# Peripheral.net
KiCad netlist of a schematic drawn in Altium Designer
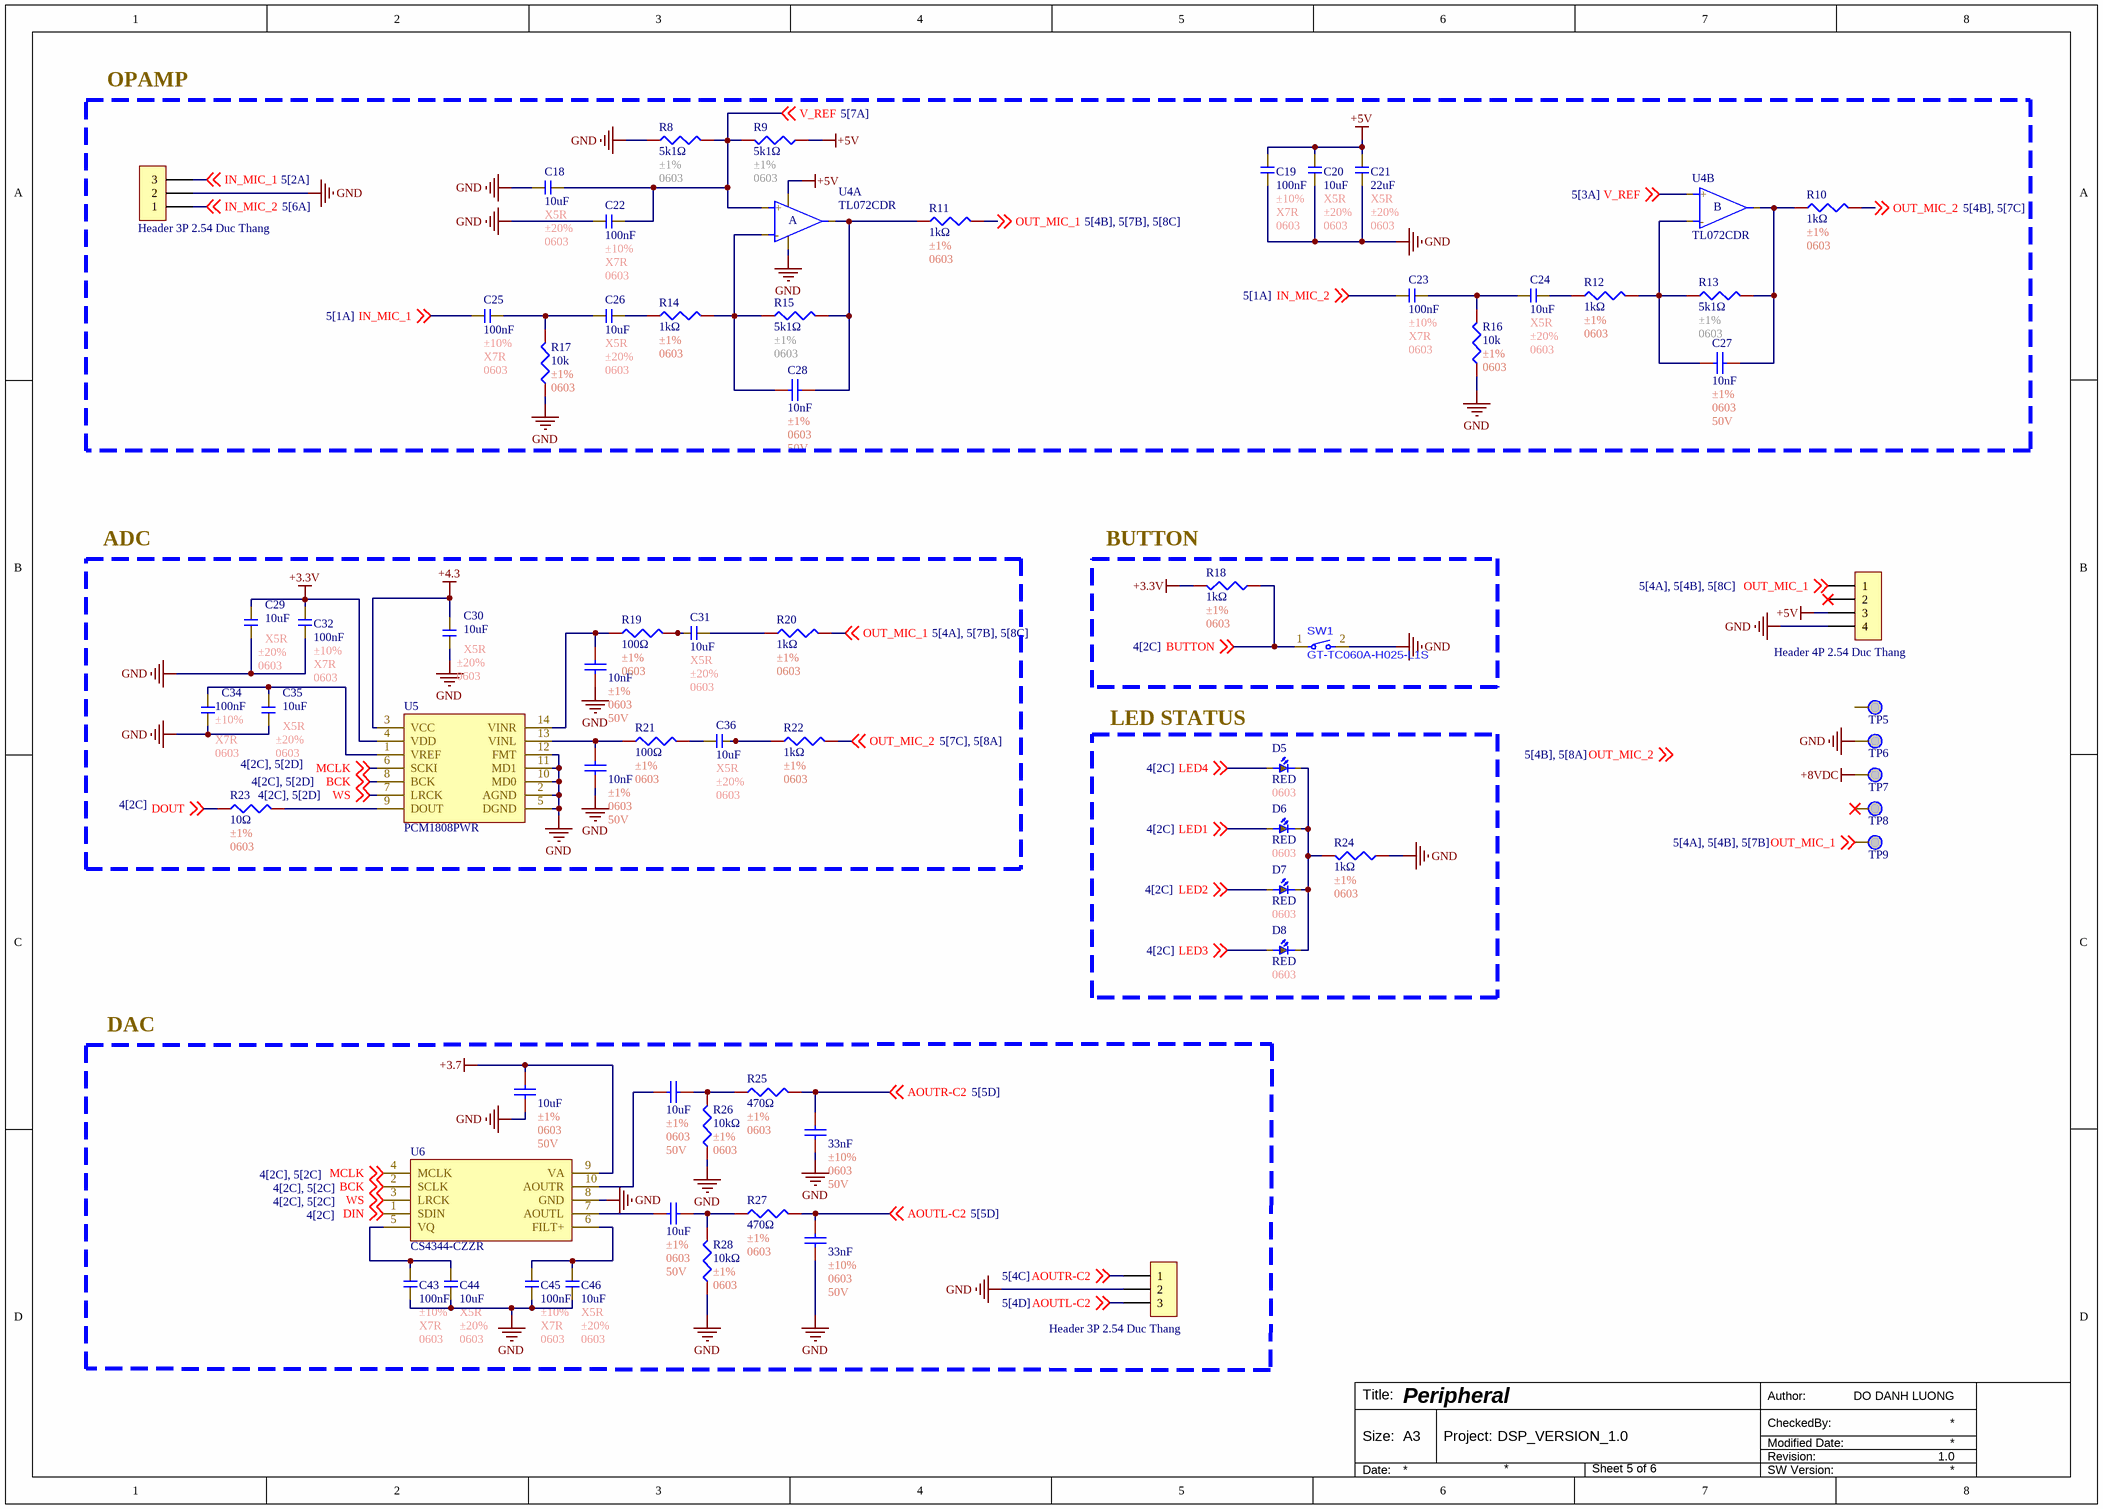
[diagram p0: Peripheral.SchDoc]

(export (version "E")
  (design (tool "Eeschema 10.0.6"))
  (components
    (comp (ref "C18")
      (value "10uF")
      (footprint "C0603")
      (description "25V 10uF X5R ±20% 0603 Multilayer Ceramic Capacitors MLCC - SMD/SMT ROHS")
      (fields
        (field (name "MANUFACTURER") "YAGEO")
        (field (name "MFR. PART #") "CC0603MRX5R8BB106")
        (field (name "TEMPERATURE COEFFICIENT") "X5R")
        (field (name "TOLERANCE") "±20%")
        (field (name "PACKAGE") "0603")
      )
      (libsource (lib "DSP_VERSION_1.0") (part "C0603_10uF_±10%_X7R"))
    )
    (comp (ref "C19")
      (value "100nF")
      (footprint "C0603")
      (description "50V 100nF X7R ±10% 0603 Multilayer Ceramic Capacitors MLCC - SMD/SMT ROHS")
      (fields
        (field (name "MANUFACTURER") "YAGEO")
        (field (name "MFR. PART #") "CC0603KRX7R9BB104")
        (field (name "TOLERANCE") "±10%")
        (field (name "TEMPERATURE COEFFICIENT") "X7R")
        (field (name "PACKAGE") "0603")
      )
      (libsource (lib "DSP_VERSION_1.0") (part "C0603_100nF_±10%_X7R"))
    )
    (comp (ref "C20")
      (value "10uF")
      (footprint "C0603")
      (description "25V 10uF X5R ±20% 0603 Multilayer Ceramic Capacitors MLCC - SMD/SMT ROHS")
      (fields
        (field (name "MANUFACTURER") "YAGEO")
        (field (name "MFR. PART #") "CC0603MRX5R8BB106")
        (field (name "TEMPERATURE COEFFICIENT") "X5R")
        (field (name "TOLERANCE") "±20%")
        (field (name "PACKAGE") "0603")
      )
      (libsource (lib "DSP_VERSION_1.0") (part "C0603_10uF_±10%_X7R"))
    )
    (comp (ref "C21")
      (value "22uF")
      (footprint "C0603")
      (description "6.3V 22uF X5R ±20% 0603 Multilayer Ceramic Capacitors MLCC - SMD/SMT ROHS")
      (fields
        (field (name "MANUFACTURER") "YAGEO")
        (field (name "MFR. PART #") "CC0603MRX5R5BB226")
        (field (name "TEMPERATURE COEFFICIENT") "X5R")
        (field (name "TOLERANCE") "±20%")
        (field (name "PACKAGE") "0603")
      )
      (libsource (lib "DSP_VERSION_1.0") (part "C0603_22uF_±20%_X5R"))
    )
    (comp (ref "C22")
      (value "100nF")
      (footprint "C0603")
      (description "50V 100nF X7R ±10% 0603 Multilayer Ceramic Capacitors MLCC - SMD/SMT ROHS")
      (fields
        (field (name "MANUFACTURER") "YAGEO")
        (field (name "MFR. PART #") "CC0603KRX7R9BB104")
        (field (name "TOLERANCE") "±10%")
        (field (name "TEMPERATURE COEFFICIENT") "X7R")
        (field (name "PACKAGE") "0603")
      )
      (libsource (lib "DSP_VERSION_1.0") (part "C0603_100nF_±10%_X7R"))
    )
    (comp (ref "C23")
      (value "100nF")
      (footprint "C0603")
      (description "50V 100nF X7R ±10% 0603 Multilayer Ceramic Capacitors MLCC - SMD/SMT ROHS")
      (fields
        (field (name "MANUFACTURER") "YAGEO")
        (field (name "MFR. PART #") "CC0603KRX7R9BB104")
        (field (name "TOLERANCE") "±10%")
        (field (name "TEMPERATURE COEFFICIENT") "X7R")
        (field (name "PACKAGE") "0603")
      )
      (libsource (lib "DSP_VERSION_1.0") (part "C0603_100nF_±10%_X7R"))
    )
    (comp (ref "C24")
      (value "10uF")
      (footprint "C0603")
      (description "25V 10uF X5R ±20% 0603 Multilayer Ceramic Capacitors MLCC - SMD/SMT ROHS")
      (fields
        (field (name "MANUFACTURER") "YAGEO")
        (field (name "MFR. PART #") "CC0603MRX5R8BB106")
        (field (name "TEMPERATURE COEFFICIENT") "X5R")
        (field (name "TOLERANCE") "±20%")
        (field (name "PACKAGE") "0603")
      )
      (libsource (lib "DSP_VERSION_1.0") (part "C0603_10uF_±10%_X7R"))
    )
    (comp (ref "C25")
      (value "100nF")
      (footprint "C0603")
      (description "50V 100nF X7R ±10% 0603 Multilayer Ceramic Capacitors MLCC - SMD/SMT ROHS")
      (fields
        (field (name "MANUFACTURER") "YAGEO")
        (field (name "MFR. PART #") "CC0603KRX7R9BB104")
        (field (name "TOLERANCE") "±10%")
        (field (name "TEMPERATURE COEFFICIENT") "X7R")
        (field (name "PACKAGE") "0603")
      )
      (libsource (lib "DSP_VERSION_1.0") (part "C0603_100nF_±10%_X7R"))
    )
    (comp (ref "C26")
      (value "10uF")
      (footprint "C0603")
      (description "25V 10uF X5R ±20% 0603 Multilayer Ceramic Capacitors MLCC - SMD/SMT ROHS")
      (fields
        (field (name "MANUFACTURER") "YAGEO")
        (field (name "MFR. PART #") "CC0603MRX5R8BB106")
        (field (name "TEMPERATURE COEFFICIENT") "X5R")
        (field (name "TOLERANCE") "±20%")
        (field (name "PACKAGE") "0603")
      )
      (libsource (lib "DSP_VERSION_1.0") (part "C0603_10uF_±10%_X7R"))
    )
    (comp (ref "C27")
      (value "10nF")
      (footprint "C0603")
      (description "50V 10pF NP0 ±1% 0402 Multilayer Ceramic Capacitors MLCC - SMD/SMT ROHS")
      (fields
        (field (name "MANUFACTURER") "YAGEO")
        (field (name "MFR. PART #") "CC0402FRNPO9BN100")
        (field (name "TOLERANCE") "±1%")
        (field (name "PACKAGE") "0603")
        (field (name "VOLTAGE RATING") "50V")
      )
      (libsource (lib "Capital") (part "C0603_10nF_±1%"))
    )
    (comp (ref "C28")
      (value "10nF")
      (footprint "C0603")
      (description "50V 10pF NP0 ±1% 0402 Multilayer Ceramic Capacitors MLCC - SMD/SMT ROHS")
      (fields
        (field (name "MANUFACTURER") "YAGEO")
        (field (name "MFR. PART #") "CC0402FRNPO9BN100")
        (field (name "TOLERANCE") "±1%")
        (field (name "PACKAGE") "0603")
        (field (name "VOLTAGE RATING") "50V")
      )
      (libsource (lib "Capital") (part "C0603_10nF_±1%"))
    )
    (comp (ref "C29")
      (value "10uF")
      (footprint "C0603")
      (description "25V 10uF X5R ±20% 0603 Multilayer Ceramic Capacitors MLCC - SMD/SMT ROHS")
      (fields
        (field (name "MANUFACTURER") "YAGEO")
        (field (name "MFR. PART #") "CC0603MRX5R8BB106")
        (field (name "TEMPERATURE COEFFICIENT") "X5R")
        (field (name "TOLERANCE") "±20%")
        (field (name "PACKAGE") "0603")
      )
      (libsource (lib "DSP_VERSION_1.0") (part "C0603_10uF_±10%_X7R"))
    )
    (comp (ref "C30")
      (value "10uF")
      (footprint "C0603")
      (description "25V 10uF X5R ±20% 0603 Multilayer Ceramic Capacitors MLCC - SMD/SMT ROHS")
      (fields
        (field (name "MANUFACTURER") "YAGEO")
        (field (name "MFR. PART #") "CC0603MRX5R8BB106")
        (field (name "TEMPERATURE COEFFICIENT") "X5R")
        (field (name "TOLERANCE") "±20%")
        (field (name "PACKAGE") "0603")
      )
      (libsource (lib "DSP_VERSION_1.0") (part "C0603_10uF_±10%_X7R"))
    )
    (comp (ref "C31")
      (value "10uF")
      (footprint "C0603")
      (description "25V 10uF X5R ±20% 0603 Multilayer Ceramic Capacitors MLCC - SMD/SMT ROHS")
      (fields
        (field (name "MANUFACTURER") "YAGEO")
        (field (name "MFR. PART #") "CC0603MRX5R8BB106")
        (field (name "TEMPERATURE COEFFICIENT") "X5R")
        (field (name "TOLERANCE") "±20%")
        (field (name "PACKAGE") "0603")
      )
      (libsource (lib "DSP_VERSION_1.0") (part "C0603_10uF_±10%_X7R"))
    )
    (comp (ref "C32")
      (value "100nF")
      (footprint "C0603")
      (description "50V 100nF X7R ±10% 0603 Multilayer Ceramic Capacitors MLCC - SMD/SMT ROHS")
      (fields
        (field (name "MANUFACTURER") "YAGEO")
        (field (name "MFR. PART #") "CC0603KRX7R9BB104")
        (field (name "TOLERANCE") "±10%")
        (field (name "TEMPERATURE COEFFICIENT") "X7R")
        (field (name "PACKAGE") "0603")
      )
      (libsource (lib "DSP_VERSION_1.0") (part "C0603_100nF_±10%_X7R"))
    )
    (comp (ref "C33")
      (value "10nF")
      (footprint "C0603")
      (description "50V 10pF NP0 ±1% 0402 Multilayer Ceramic Capacitors MLCC - SMD/SMT ROHS")
      (fields
        (field (name "MANUFACTURER") "YAGEO")
        (field (name "MFR. PART #") "CC0402FRNPO9BN100")
        (field (name "TOLERANCE") "±1%")
        (field (name "PACKAGE") "0603")
        (field (name "VOLTAGE RATING") "50V")
      )
      (libsource (lib "Capital") (part "C0603_10nF_±1%"))
    )
    (comp (ref "C34")
      (value "100nF")
      (footprint "C0603")
      (description "50V 100nF X7R ±10% 0603 Multilayer Ceramic Capacitors MLCC - SMD/SMT ROHS")
      (fields
        (field (name "MANUFACTURER") "YAGEO")
        (field (name "MFR. PART #") "CC0603KRX7R9BB104")
        (field (name "TOLERANCE") "±10%")
        (field (name "TEMPERATURE COEFFICIENT") "X7R")
        (field (name "PACKAGE") "0603")
      )
      (libsource (lib "DSP_VERSION_1.0") (part "C0603_100nF_±10%_X7R"))
    )
    (comp (ref "C35")
      (value "10uF")
      (footprint "C0603")
      (description "25V 10uF X5R ±20% 0603 Multilayer Ceramic Capacitors MLCC - SMD/SMT ROHS")
      (fields
        (field (name "MANUFACTURER") "YAGEO")
        (field (name "MFR. PART #") "CC0603MRX5R8BB106")
        (field (name "TEMPERATURE COEFFICIENT") "X5R")
        (field (name "TOLERANCE") "±20%")
        (field (name "PACKAGE") "0603")
      )
      (libsource (lib "DSP_VERSION_1.0") (part "C0603_10uF_±10%_X7R"))
    )
    (comp (ref "C36")
      (value "10uF")
      (footprint "C0603")
      (description "25V 10uF X5R ±20% 0603 Multilayer Ceramic Capacitors MLCC - SMD/SMT ROHS")
      (fields
        (field (name "MANUFACTURER") "YAGEO")
        (field (name "MFR. PART #") "CC0603MRX5R8BB106")
        (field (name "TEMPERATURE COEFFICIENT") "X5R")
        (field (name "TOLERANCE") "±20%")
        (field (name "PACKAGE") "0603")
      )
      (libsource (lib "DSP_VERSION_1.0") (part "C0603_10uF_±10%_X7R"))
    )
    (comp (ref "C37")
      (value "10nF")
      (footprint "C0603")
      (description "50V 10pF NP0 ±1% 0402 Multilayer Ceramic Capacitors MLCC - SMD/SMT ROHS")
      (fields
        (field (name "MANUFACTURER") "YAGEO")
        (field (name "MFR. PART #") "CC0402FRNPO9BN100")
        (field (name "TOLERANCE") "±1%")
        (field (name "PACKAGE") "0603")
        (field (name "VOLTAGE RATING") "50V")
      )
      (libsource (lib "Capital") (part "C0603_10nF_±1%"))
    )
    (comp (ref "C38")
      (value "10uF")
      (footprint "C0603")
      (description "50V 10pF NP0 ±1% 0402 Multilayer Ceramic Capacitors MLCC - SMD/SMT ROHS")
      (fields
        (field (name "MANUFACTURER") "YAGEO")
        (field (name "MFR. PART #") "CC0402FRNPO9BN100")
        (field (name "TOLERANCE") "±1%")
        (field (name "PACKAGE") "0603")
        (field (name "VOLTAGE RATING") "50V")
      )
      (libsource (lib "Capital") (part "C0603_10uF_±1%"))
    )
    (comp (ref "C39")
      (value "10uF")
      (footprint "C0603")
      (description "50V 10pF NP0 ±1% 0402 Multilayer Ceramic Capacitors MLCC - SMD/SMT ROHS")
      (fields
        (field (name "MANUFACTURER") "YAGEO")
        (field (name "MFR. PART #") "CC0402FRNPO9BN100")
        (field (name "TOLERANCE") "±1%")
        (field (name "PACKAGE") "0603")
        (field (name "VOLTAGE RATING") "50V")
      )
      (libsource (lib "Capital") (part "C0603_10uF_±1%"))
    )
    (comp (ref "C40")
      (value "33nF")
      (footprint "C0603")
      (description "100mW Thick Film Resistor 75V ±100ppm/℃ ±1% 470Ω 0603 Chip Resistor - Surface Mount ROHS")
      (fields
        (field (name "MANUFACTURER") "YAGEO")
        (field (name "MFR. PART #") "CC0603KRX7R9BB333")
        (field (name "TOLERANCE") "±10%")
        (field (name "PACKAGE") "0603")
        (field (name "VOLTAGE RATING") "50V")
      )
      (libsource (lib "Capital") (part "C0603_33nF_±10%"))
    )
    (comp (ref "C41")
      (value "10uF")
      (footprint "C0603")
      (description "50V 10pF NP0 ±1% 0402 Multilayer Ceramic Capacitors MLCC - SMD/SMT ROHS")
      (fields
        (field (name "MANUFACTURER") "YAGEO")
        (field (name "MFR. PART #") "CC0402FRNPO9BN100")
        (field (name "TOLERANCE") "±1%")
        (field (name "PACKAGE") "0603")
        (field (name "VOLTAGE RATING") "50V")
      )
      (libsource (lib "Capital") (part "C0603_10uF_±1%"))
    )
    (comp (ref "C42")
      (value "33nF")
      (footprint "C0603")
      (description "100mW Thick Film Resistor 75V ±100ppm/℃ ±1% 470Ω 0603 Chip Resistor - Surface Mount ROHS")
      (fields
        (field (name "MANUFACTURER") "YAGEO")
        (field (name "MFR. PART #") "CC0603KRX7R9BB333")
        (field (name "TOLERANCE") "±10%")
        (field (name "PACKAGE") "0603")
        (field (name "VOLTAGE RATING") "50V")
      )
      (libsource (lib "Capital") (part "C0603_33nF_±10%"))
    )
    (comp (ref "C43")
      (value "100nF")
      (footprint "C0603")
      (description "50V 100nF X7R ±10% 0603 Multilayer Ceramic Capacitors MLCC - SMD/SMT ROHS")
      (fields
        (field (name "MANUFACTURER") "YAGEO")
        (field (name "MFR. PART #") "CC0603KRX7R9BB104")
        (field (name "TOLERANCE") "±10%")
        (field (name "TEMPERATURE COEFFICIENT") "X7R")
        (field (name "PACKAGE") "0603")
      )
      (libsource (lib "DSP_VERSION_1.0") (part "C0603_100nF_±10%_X7R"))
    )
    (comp (ref "C44")
      (value "10uF")
      (footprint "C0603")
      (description "25V 10uF X5R ±20% 0603 Multilayer Ceramic Capacitors MLCC - SMD/SMT ROHS")
      (fields
        (field (name "MANUFACTURER") "YAGEO")
        (field (name "MFR. PART #") "CC0603MRX5R8BB106")
        (field (name "TEMPERATURE COEFFICIENT") "X5R")
        (field (name "TOLERANCE") "±20%")
        (field (name "PACKAGE") "0603")
      )
      (libsource (lib "DSP_VERSION_1.0") (part "C0603_10uF_±10%_X7R"))
    )
    (comp (ref "C45")
      (value "100nF")
      (footprint "C0603")
      (description "50V 100nF X7R ±10% 0603 Multilayer Ceramic Capacitors MLCC - SMD/SMT ROHS")
      (fields
        (field (name "MANUFACTURER") "YAGEO")
        (field (name "MFR. PART #") "CC0603KRX7R9BB104")
        (field (name "TOLERANCE") "±10%")
        (field (name "TEMPERATURE COEFFICIENT") "X7R")
        (field (name "PACKAGE") "0603")
      )
      (libsource (lib "DSP_VERSION_1.0") (part "C0603_100nF_±10%_X7R"))
    )
    (comp (ref "C46")
      (value "10uF")
      (footprint "C0603")
      (description "25V 10uF X5R ±20% 0603 Multilayer Ceramic Capacitors MLCC - SMD/SMT ROHS")
      (fields
        (field (name "MANUFACTURER") "YAGEO")
        (field (name "MFR. PART #") "CC0603MRX5R8BB106")
        (field (name "TEMPERATURE COEFFICIENT") "X5R")
        (field (name "TOLERANCE") "±20%")
        (field (name "PACKAGE") "0603")
      )
      (libsource (lib "DSP_VERSION_1.0") (part "C0603_10uF_±10%_X7R"))
    )
    (comp (ref "D5")
      (value "RED")
      (footprint "LED0603")
      (description "25mcd~40mcd Water Clear -40℃~+85℃ 624nm Red 120° 60mW 0402 LED Indication - Discrete ROHS")
      (fields
        (field (name "MANUFACTURER") "XINGLIGHT")
        (field (name "MFR. PART #") "XL-1005UGC")
        (field (name "PACKAGE") "0603")
      )
      (libsource (lib "LED") (part "D0603_RED"))
    )
    (comp (ref "D6")
      (value "RED")
      (footprint "LED0603")
      (description "25mcd~40mcd Water Clear -40℃~+85℃ 624nm Red 120° 60mW 0402 LED Indication - Discrete ROHS")
      (fields
        (field (name "MANUFACTURER") "XINGLIGHT")
        (field (name "MFR. PART #") "XL-1005UGC")
        (field (name "PACKAGE") "0603")
      )
      (libsource (lib "LED") (part "D0603_RED"))
    )
    (comp (ref "D7")
      (value "RED")
      (footprint "LED0603")
      (description "25mcd~40mcd Water Clear -40℃~+85℃ 624nm Red 120° 60mW 0402 LED Indication - Discrete ROHS")
      (fields
        (field (name "MANUFACTURER") "XINGLIGHT")
        (field (name "MFR. PART #") "XL-1005UGC")
        (field (name "PACKAGE") "0603")
      )
      (libsource (lib "LED") (part "D0603_RED"))
    )
    (comp (ref "D8")
      (value "RED")
      (footprint "LED0603")
      (description "25mcd~40mcd Water Clear -40℃~+85℃ 624nm Red 120° 60mW 0402 LED Indication - Discrete ROHS")
      (fields
        (field (name "MANUFACTURER") "XINGLIGHT")
        (field (name "MFR. PART #") "XL-1005UGC")
        (field (name "PACKAGE") "0603")
      )
      (libsource (lib "LED") (part "D0603_RED"))
    )
    (comp (ref "H1")
      (value "Header 3P 2.54 Duc Thang")
      (footprint "XH2.54M-3")
      (description "Cắm")
      (libsource (lib "Header") (part "Header 3P 2.54 Duc Thang"))
    )
    (comp (ref "H2")
      (value "Header 4P 2.54 Duc Thang")
      (footprint "XH2.54M-4")
      (description "Cắm")
      (libsource (lib "Header") (part "Header 4P 2.54 Duc Thang"))
    )
    (comp (ref "H3")
      (value "Header 3P 2.54 Duc Thang")
      (footprint "XH2.54M-3")
      (description "Cắm")
      (libsource (lib "") (part "Header 3P 2.54 Duc Thang_1"))
    )
    (comp (ref "R8")
      (value "5k1Ω")
      (footprint "R0603")
      (description "100mW Thick Film Resistor 75V ±100ppm/℃ ±1% 5.1kΩ 0603 Chip Resistor - Surface Mount ROHS")
      (fields
        (field (name "MANUFACTURER") "FOJAN")
        (field (name "MFR. PART #") "FRC0603F5101TS")
        (field (name "TOLERANCE") "±1%")
        (field (name "PACKAGE") "0603")
      )
      (libsource (lib "Resistor") (part "R0603_5k1Ω_±1%"))
    )
    (comp (ref "R9")
      (value "5k1Ω")
      (footprint "R0603")
      (description "100mW Thick Film Resistor 75V ±100ppm/℃ ±1% 5.1kΩ 0603 Chip Resistor - Surface Mount ROHS")
      (fields
        (field (name "MANUFACTURER") "FOJAN")
        (field (name "MFR. PART #") "FRC0603F5101TS")
        (field (name "TOLERANCE") "±1%")
        (field (name "PACKAGE") "0603")
      )
      (libsource (lib "Resistor") (part "R0603_5k1Ω_±1%"))
    )
    (comp (ref "R10")
      (value "1kΩ")
      (footprint "R0603")
      (description "62.5mW Thick Film Resistor 50V ±1% ±200ppm/℃ 10Ω 0402 Chip Resistor - Surface Mount ROHS")
      (fields
        (field (name "MANUFACTURER") "YAGEO")
        (field (name "MFR. PART #") "RC0402FR-0710RL")
        (field (name "TOLERANCE") "±1%")
        (field (name "PACKAGE") "0603")
      )
      (libsource (lib "Resistor") (part "R0603_1kΩ_±1%"))
    )
    (comp (ref "R11")
      (value "1kΩ")
      (footprint "R0603")
      (description "62.5mW Thick Film Resistor 50V ±1% ±200ppm/℃ 10Ω 0402 Chip Resistor - Surface Mount ROHS")
      (fields
        (field (name "MANUFACTURER") "YAGEO")
        (field (name "MFR. PART #") "RC0402FR-0710RL")
        (field (name "TOLERANCE") "±1%")
        (field (name "PACKAGE") "0603")
      )
      (libsource (lib "Resistor") (part "R0603_1kΩ_±1%"))
    )
    (comp (ref "R12")
      (value "1kΩ")
      (footprint "R0603")
      (description "62.5mW Thick Film Resistor 50V ±1% ±200ppm/℃ 10Ω 0402 Chip Resistor - Surface Mount ROHS")
      (fields
        (field (name "MANUFACTURER") "YAGEO")
        (field (name "MFR. PART #") "RC0402FR-0710RL")
        (field (name "TOLERANCE") "±1%")
        (field (name "PACKAGE") "0603")
      )
      (libsource (lib "Resistor") (part "R0603_1kΩ_±1%"))
    )
    (comp (ref "R13")
      (value "5k1Ω")
      (footprint "R0603")
      (description "100mW Thick Film Resistor 75V ±100ppm/℃ ±1% 5.1kΩ 0603 Chip Resistor - Surface Mount ROHS")
      (fields
        (field (name "MANUFACTURER") "FOJAN")
        (field (name "MFR. PART #") "FRC0603F5101TS")
        (field (name "TOLERANCE") "±1%")
        (field (name "PACKAGE") "0603")
      )
      (libsource (lib "Resistor") (part "R0603_5k1Ω_±1%"))
    )
    (comp (ref "R14")
      (value "1kΩ")
      (footprint "R0603")
      (description "62.5mW Thick Film Resistor 50V ±1% ±200ppm/℃ 10Ω 0402 Chip Resistor - Surface Mount ROHS")
      (fields
        (field (name "MANUFACTURER") "YAGEO")
        (field (name "MFR. PART #") "RC0402FR-0710RL")
        (field (name "TOLERANCE") "±1%")
        (field (name "PACKAGE") "0603")
      )
      (libsource (lib "Resistor") (part "R0603_1kΩ_±1%"))
    )
    (comp (ref "R15")
      (value "5k1Ω")
      (footprint "R0603")
      (description "100mW Thick Film Resistor 75V ±100ppm/℃ ±1% 5.1kΩ 0603 Chip Resistor - Surface Mount ROHS")
      (fields
        (field (name "MANUFACTURER") "FOJAN")
        (field (name "MFR. PART #") "FRC0603F5101TS")
        (field (name "TOLERANCE") "±1%")
        (field (name "PACKAGE") "0603")
      )
      (libsource (lib "Resistor") (part "R0603_5k1Ω_±1%"))
    )
    (comp (ref "R16")
      (value "10k")
      (footprint "R0603")
      (description "62.5mW Thick Film Resistor 50V ±1% ±200ppm/℃ 10Ω 0402 Chip Resistor - Surface Mount ROHS")
      (fields
        (field (name "MANUFACTURER") "YAGEO")
        (field (name "MFR. PART #") "RC0402FR-0710RL")
        (field (name "TOLERANCE") "±1%")
        (field (name "PACKAGE") "0603")
      )
      (libsource (lib "Resistor") (part "R0603_1kΩ_±1%"))
    )
    (comp (ref "R17")
      (value "10k")
      (footprint "R0603")
      (description "62.5mW Thick Film Resistor 50V ±1% ±200ppm/℃ 10Ω 0402 Chip Resistor - Surface Mount ROHS")
      (fields
        (field (name "MANUFACTURER") "YAGEO")
        (field (name "MFR. PART #") "RC0402FR-0710RL")
        (field (name "TOLERANCE") "±1%")
        (field (name "PACKAGE") "0603")
      )
      (libsource (lib "Resistor") (part "R0603_1kΩ_±1%"))
    )
    (comp (ref "R18")
      (value "1kΩ")
      (footprint "R0603")
      (description "62.5mW Thick Film Resistor 50V ±1% ±200ppm/℃ 10Ω 0402 Chip Resistor - Surface Mount ROHS")
      (fields
        (field (name "MANUFACTURER") "YAGEO")
        (field (name "MFR. PART #") "RC0402FR-0710RL")
        (field (name "TOLERANCE") "±1%")
        (field (name "PACKAGE") "0603")
      )
      (libsource (lib "Resistor") (part "R0603_1kΩ_±1%"))
    )
    (comp (ref "R19")
      (value "100Ω")
      (footprint "R0603")
      (description "62.5mW Thick Film Resistor 50V ±1% ±200ppm/℃ 10Ω 0402 Chip Resistor - Surface Mount ROHS")
      (fields
        (field (name "MANUFACTURER") "YAGEO")
        (field (name "MFR. PART #") "RC0402FR-0710RL")
        (field (name "TOLERANCE") "±1%")
        (field (name "PACKAGE") "0603")
      )
      (libsource (lib "Resistor") (part "R0603_100Ω_±1%"))
    )
    (comp (ref "R20")
      (value "1kΩ")
      (footprint "R0603")
      (description "62.5mW Thick Film Resistor 50V ±1% ±200ppm/℃ 10Ω 0402 Chip Resistor - Surface Mount ROHS")
      (fields
        (field (name "MANUFACTURER") "YAGEO")
        (field (name "MFR. PART #") "RC0402FR-0710RL")
        (field (name "TOLERANCE") "±1%")
        (field (name "PACKAGE") "0603")
      )
      (libsource (lib "Resistor") (part "R0603_1kΩ_±1%"))
    )
    (comp (ref "R21")
      (value "100Ω")
      (footprint "R0603")
      (description "62.5mW Thick Film Resistor 50V ±1% ±200ppm/℃ 10Ω 0402 Chip Resistor - Surface Mount ROHS")
      (fields
        (field (name "MANUFACTURER") "YAGEO")
        (field (name "MFR. PART #") "RC0402FR-0710RL")
        (field (name "TOLERANCE") "±1%")
        (field (name "PACKAGE") "0603")
      )
      (libsource (lib "Resistor") (part "R0603_100Ω_±1%"))
    )
    (comp (ref "R22")
      (value "1kΩ")
      (footprint "R0603")
      (description "62.5mW Thick Film Resistor 50V ±1% ±200ppm/℃ 10Ω 0402 Chip Resistor - Surface Mount ROHS")
      (fields
        (field (name "MANUFACTURER") "YAGEO")
        (field (name "MFR. PART #") "RC0402FR-0710RL")
        (field (name "TOLERANCE") "±1%")
        (field (name "PACKAGE") "0603")
      )
      (libsource (lib "Resistor") (part "R0603_1kΩ_±1%"))
    )
    (comp (ref "R23")
      (value "10Ω")
      (footprint "R0603")
      (description "62.5mW Thick Film Resistor 50V ±1% ±200ppm/℃ 10Ω 0402 Chip Resistor - Surface Mount ROHS")
      (fields
        (field (name "MANUFACTURER") "YAGEO")
        (field (name "MFR. PART #") "RC0402FR-0710RL")
        (field (name "TOLERANCE") "±1%")
        (field (name "PACKAGE") "0603")
      )
      (libsource (lib "Resistor") (part "R0603_10Ω_±1%"))
    )
    (comp (ref "R24")
      (value "1kΩ")
      (footprint "R0603")
      (description "62.5mW Thick Film Resistor 50V ±1% ±200ppm/℃ 10Ω 0402 Chip Resistor - Surface Mount ROHS")
      (fields
        (field (name "MANUFACTURER") "YAGEO")
        (field (name "MFR. PART #") "RC0402FR-0710RL")
        (field (name "TOLERANCE") "±1%")
        (field (name "PACKAGE") "0603")
      )
      (libsource (lib "Resistor") (part "R0603_1kΩ_±1%"))
    )
    (comp (ref "R25")
      (value "470Ω")
      (footprint "R0603")
      (description "62.5mW Thick Film Resistor 50V ±1% ±200ppm/℃ 10Ω 0402 Chip Resistor - Surface Mount ROHS")
      (fields
        (field (name "MANUFACTURER") "YAGEO")
        (field (name "MFR. PART #") "RC0603FR-07470RL")
        (field (name "TOLERANCE") "±1%")
        (field (name "PACKAGE") "0603")
      )
      (libsource (lib "Resistor") (part "R0603_470Ω_±1%_1"))
    )
    (comp (ref "R26")
      (value "10kΩ")
      (footprint "R0603")
      (description "62.5mW Thick Film Resistor 50V ±1% ±200ppm/℃ 10Ω 0402 Chip Resistor - Surface Mount ROHS")
      (fields
        (field (name "MANUFACTURER") "YAGEO")
        (field (name "MFR. PART #") "RC0402FR-0710RL")
        (field (name "TOLERANCE") "±1%")
        (field (name "PACKAGE") "0603")
      )
      (libsource (lib "Resistor") (part "R0603_10kΩ_±1%"))
    )
    (comp (ref "R27")
      (value "470Ω")
      (footprint "R0603")
      (description "62.5mW Thick Film Resistor 50V ±1% ±200ppm/℃ 10Ω 0402 Chip Resistor - Surface Mount ROHS")
      (fields
        (field (name "MANUFACTURER") "YAGEO")
        (field (name "MFR. PART #") "RC0603FR-07470RL")
        (field (name "TOLERANCE") "±1%")
        (field (name "PACKAGE") "0603")
      )
      (libsource (lib "Resistor") (part "R0603_470Ω_±1%_1"))
    )
    (comp (ref "R28")
      (value "10kΩ")
      (footprint "R0603")
      (description "62.5mW Thick Film Resistor 50V ±1% ±200ppm/℃ 10Ω 0402 Chip Resistor - Surface Mount ROHS")
      (fields
        (field (name "MANUFACTURER") "YAGEO")
        (field (name "MFR. PART #") "RC0402FR-0710RL")
        (field (name "TOLERANCE") "±1%")
        (field (name "PACKAGE") "0603")
      )
      (libsource (lib "Resistor") (part "R0603_10kΩ_±1%"))
    )
    (comp (ref "SW1")
      (value "GT-TC060A-H025-L1S")
      (footprint "GT-TC060A-H025-L1S")
      (description "Tactile Switch SPST 160gf 2.5mm SMD (SMT) Tab 6.05mm x 3.5mm Surface Mount")
      (fields (field (name "MANUFACTURER") "G-Switch") (field (name "LCSC PART #") "C7450623"))
      (libsource (lib "Switch") (part "GT-TC060A-H025-L1S"))
    )
    (comp (ref "TP5") (value "TP") (footprint "TP") (libsource (lib "Other") (part "TP")))
    (comp (ref "TP6") (value "TP") (footprint "TP") (libsource (lib "Other") (part "TP")))
    (comp (ref "TP7") (value "TP") (footprint "TP") (libsource (lib "Other") (part "TP")))
    (comp (ref "TP8") (value "TP") (footprint "TP") (libsource (lib "Other") (part "TP")))
    (comp (ref "TP9") (value "TP") (footprint "TP") (libsource (lib "Other") (part "TP")))
    (comp (ref "U4")
      (value "TL072CDR")
      (footprint "TL072CDR")
      (description "3mV 65pA 3MHz 13V/us 2 SOIC-8 FET Input Amplifiers ROHS")
      (fields (field (name "MANUFACTURER") "TI") (field (name "LCSC PART #") "C67473"))
      (libsource (lib "IC") (part "TL072CDR"))
    )
    (comp (ref "U5")
      (value "PCM1808PWR")
      (footprint "PCM1808PWR")
      (description "4.5V~5.5V 24 I2S TSSOP-14 ADCs/DACs - Special Purpose ROHS")
      (fields (field (name "MANUFACTURER") "TI") (field (name "LCSC PART #") "C55513"))
      (libsource (lib "IC") (part "PCM1808PWR"))
    )
    (comp (ref "U6")
      (value "CS4344-CZZR")
      (footprint "CS4344-CZZR")
      (description "250ms I2S 3.3V~5V 24 TSSOP-10-3mm Digital to Analog Converters (DAC) ROHS")
      (fields (field (name "MANUFACTURER") "Cirrus Logic") (field (name "LCSC PART #") "C8952"))
      (libsource (lib "IC") (part "CS4344-CZZR"))
    )
  )
  (nets
    (net (code "1") (name "+3.3V") (class "Default")
      (node (ref "C29") (pin "2") (pinfunction "2_2") (pintype "passive"))
      (node (ref "C32") (pin "2") (pinfunction "2_2") (pintype "passive"))
      (node (ref "R18") (pin "2") (pinfunction "2_2") (pintype "passive"))
      (node (ref "U5") (pin "4") (pinfunction "VDD_4") (pintype "passive"))
    )
    (net (code "2") (name "+3.7") (class "Default")
      (node (ref "C39") (pin "1") (pinfunction "1_1") (pintype "passive"))
      (node (ref "U6") (pin "9") (pinfunction "VA_9") (pintype "passive"))
    )
    (net (code "3") (name "+4.3") (class "Default")
      (node (ref "C30") (pin "2") (pinfunction "2_2") (pintype "passive"))
      (node (ref "U5") (pin "3") (pinfunction "VCC_3") (pintype "passive"))
    )
    (net (code "4") (name "+5V") (class "Default")
      (node (ref "C19") (pin "2") (pinfunction "2_2") (pintype "passive"))
      (node (ref "C20") (pin "2") (pinfunction "2_2") (pintype "passive"))
      (node (ref "C21") (pin "2") (pinfunction "2_2") (pintype "passive"))
      (node (ref "H2") (pin "3") (pinfunction "3_3") (pintype "passive"))
      (node (ref "R9") (pin "1") (pinfunction "1_1") (pintype "passive"))
      (node (ref "U4") (pin "8") (pinfunction "8_8") (pintype "passive"))
    )
    (net (code "5") (name "+8VDC") (class "Default")
      (node (ref "TP7") (pin "1") (pinfunction "1_1") (pintype "passive"))
    )
    (net (code "6") (name "AOUTL-C2") (class "Default")
      (node (ref "C42") (pin "1") (pinfunction "1_1") (pintype "passive"))
      (node (ref "H3") (pin "3") (pinfunction "3_3") (pintype "passive"))
      (node (ref "R27") (pin "2") (pinfunction "2_2") (pintype "passive"))
    )
    (net (code "7") (name "AOUTR-C2") (class "Default")
      (node (ref "C40") (pin "1") (pinfunction "1_1") (pintype "passive"))
      (node (ref "H3") (pin "1") (pinfunction "1_1") (pintype "passive"))
      (node (ref "R25") (pin "2") (pinfunction "2_2") (pintype "passive"))
    )
    (net (code "8") (name "BCK") (class "Default")
      (node (ref "U5") (pin "8") (pinfunction "BCK_8") (pintype "passive"))
      (node (ref "U6") (pin "2") (pinfunction "SCLK_2") (pintype "passive"))
    )
    (net (code "9") (name "BUTTON") (class "Default")
      (node (ref "R18") (pin "1") (pinfunction "1_1") (pintype "passive"))
      (node (ref "SW1") (pin "1") (pinfunction "1_1") (pintype "passive"))
    )
    (net (code "10") (name "DIN") (class "Default")
      (node (ref "U6") (pin "1") (pinfunction "SDIN_1") (pintype "passive"))
    )
    (net (code "11") (name "DOUT") (class "Default")
      (node (ref "R23") (pin "1") (pinfunction "1_1") (pintype "passive"))
    )
    (net (code "12") (name "GND") (class "Default")
      (node (ref "C18") (pin "2") (pinfunction "2_2") (pintype "passive"))
      (node (ref "C19") (pin "1") (pinfunction "1_1") (pintype "passive"))
      (node (ref "C20") (pin "1") (pinfunction "1_1") (pintype "passive"))
      (node (ref "C21") (pin "1") (pinfunction "1_1") (pintype "passive"))
      (node (ref "C22") (pin "2") (pinfunction "2_2") (pintype "passive"))
      (node (ref "C29") (pin "1") (pinfunction "1_1") (pintype "passive"))
      (node (ref "C30") (pin "1") (pinfunction "1_1") (pintype "passive"))
      (node (ref "C32") (pin "1") (pinfunction "1_1") (pintype "passive"))
      (node (ref "C33") (pin "2") (pinfunction "2_2") (pintype "passive"))
      (node (ref "C34") (pin "1") (pinfunction "1_1") (pintype "passive"))
      (node (ref "C35") (pin "1") (pinfunction "1_1") (pintype "passive"))
      (node (ref "C37") (pin "2") (pinfunction "2_2") (pintype "passive"))
      (node (ref "C39") (pin "2") (pinfunction "2_2") (pintype "passive"))
      (node (ref "C40") (pin "2") (pinfunction "2_2") (pintype "passive"))
      (node (ref "C42") (pin "2") (pinfunction "2_2") (pintype "passive"))
      (node (ref "C43") (pin "1") (pinfunction "1_1") (pintype "passive"))
      (node (ref "C44") (pin "1") (pinfunction "1_1") (pintype "passive"))
      (node (ref "C45") (pin "1") (pinfunction "1_1") (pintype "passive"))
      (node (ref "C46") (pin "1") (pinfunction "1_1") (pintype "passive"))
      (node (ref "H1") (pin "2") (pinfunction "2_2") (pintype "passive"))
      (node (ref "H2") (pin "4") (pinfunction "4_4") (pintype "passive"))
      (node (ref "H3") (pin "2") (pinfunction "2_2") (pintype "passive"))
      (node (ref "R16") (pin "1") (pinfunction "1_1") (pintype "passive"))
      (node (ref "R17") (pin "1") (pinfunction "1_1") (pintype "passive"))
      (node (ref "R24") (pin "1") (pinfunction "1_1") (pintype "passive"))
      (node (ref "R26") (pin "1") (pinfunction "1_1") (pintype "passive"))
      (node (ref "R28") (pin "1") (pinfunction "1_1") (pintype "passive"))
      (node (ref "R8") (pin "1") (pinfunction "1_1") (pintype "passive"))
      (node (ref "SW1") (pin "2") (pinfunction "2_2") (pintype "passive"))
      (node (ref "TP6") (pin "1") (pinfunction "1_1") (pintype "passive"))
      (node (ref "U4") (pin "4") (pinfunction "GND_4") (pintype "passive"))
      (node (ref "U5") (pin "10") (pinfunction "MD0_10") (pintype "passive"))
      (node (ref "U5") (pin "11") (pinfunction "MD1_11") (pintype "passive"))
      (node (ref "U5") (pin "12") (pinfunction "FMT_12") (pintype "passive"))
      (node (ref "U5") (pin "2") (pinfunction "AGND_2") (pintype "passive"))
      (node (ref "U5") (pin "5") (pinfunction "DGND_5") (pintype "passive"))
      (node (ref "U6") (pin "8") (pinfunction "GND_8") (pintype "passive"))
    )
    (net (code "13") (name "IN_MIC_1") (class "Default")
      (node (ref "C25") (pin "2") (pinfunction "2_2") (pintype "passive"))
      (node (ref "H1") (pin "3") (pinfunction "3_3") (pintype "passive"))
    )
    (net (code "14") (name "IN_MIC_2") (class "Default")
      (node (ref "C23") (pin "2") (pinfunction "2_2") (pintype "passive"))
      (node (ref "H1") (pin "1") (pinfunction "1_1") (pintype "passive"))
    )
    (net (code "15") (name "LED1") (class "Default")
      (node (ref "D6") (pin "2") (pinfunction "2_2") (pintype "passive"))
    )
    (net (code "16") (name "LED2") (class "Default")
      (node (ref "D7") (pin "2") (pinfunction "2_2") (pintype "passive"))
    )
    (net (code "17") (name "LED3") (class "Default")
      (node (ref "D8") (pin "2") (pinfunction "2_2") (pintype "passive"))
    )
    (net (code "18") (name "LED4") (class "Default")
      (node (ref "D5") (pin "2") (pinfunction "2_2") (pintype "passive"))
    )
    (net (code "19") (name "MCLK") (class "Default")
      (node (ref "U5") (pin "6") (pinfunction "SCKI_6") (pintype "passive"))
      (node (ref "U6") (pin "4") (pinfunction "MCLK_4") (pintype "passive"))
    )
    (net (code "20") (name "Net-(C23-Pad1)") (class "Default")
      (node (ref "C23") (pin "1") (pinfunction "1_1") (pintype "passive"))
      (node (ref "C24") (pin "2") (pinfunction "2_2") (pintype "passive"))
      (node (ref "R16") (pin "2") (pinfunction "2_2") (pintype "passive"))
    )
    (net (code "21") (name "Net-(C24-Pad1)") (class "Default")
      (node (ref "C24") (pin "1") (pinfunction "1_1") (pintype "passive"))
      (node (ref "R12") (pin "1") (pinfunction "1_1") (pintype "passive"))
    )
    (net (code "22") (name "Net-(C25-Pad1)") (class "Default")
      (node (ref "C25") (pin "1") (pinfunction "1_1") (pintype "passive"))
      (node (ref "C26") (pin "2") (pinfunction "2_2") (pintype "passive"))
      (node (ref "R17") (pin "2") (pinfunction "2_2") (pintype "passive"))
    )
    (net (code "23") (name "Net-(C26-Pad1)") (class "Default")
      (node (ref "C26") (pin "1") (pinfunction "1_1") (pintype "passive"))
      (node (ref "R14") (pin "1") (pinfunction "1_1") (pintype "passive"))
    )
    (net (code "24") (name "Net-(C31-Pad1)") (class "Default")
      (node (ref "C31") (pin "1") (pinfunction "1_1") (pintype "passive"))
      (node (ref "R20") (pin "1") (pinfunction "1_1") (pintype "passive"))
    )
    (net (code "25") (name "Net-(C31-Pad2)") (class "Default")
      (node (ref "C31") (pin "2") (pinfunction "2_2") (pintype "passive"))
      (node (ref "R19") (pin "2") (pinfunction "2_2") (pintype "passive"))
    )
    (net (code "26") (name "Net-(C36-Pad1)") (class "Default")
      (node (ref "C36") (pin "1") (pinfunction "1_1") (pintype "passive"))
      (node (ref "R22") (pin "1") (pinfunction "1_1") (pintype "passive"))
    )
    (net (code "27") (name "Net-(C36-Pad2)") (class "Default")
      (node (ref "C36") (pin "2") (pinfunction "2_2") (pintype "passive"))
      (node (ref "R21") (pin "2") (pinfunction "2_2") (pintype "passive"))
    )
    (net (code "28") (name "Net-(C38-Pad1)") (class "Default")
      (node (ref "C38") (pin "1") (pinfunction "1_1") (pintype "passive"))
      (node (ref "R25") (pin "1") (pinfunction "1_1") (pintype "passive"))
      (node (ref "R26") (pin "2") (pinfunction "2_2") (pintype "passive"))
    )
    (net (code "29") (name "Net-(C41-Pad1)") (class "Default")
      (node (ref "C41") (pin "1") (pinfunction "1_1") (pintype "passive"))
      (node (ref "R27") (pin "1") (pinfunction "1_1") (pintype "passive"))
      (node (ref "R28") (pin "2") (pinfunction "2_2") (pintype "passive"))
    )
    (net (code "30") (name "Net-(D5-Pad1)") (class "Default")
      (node (ref "D5") (pin "1") (pinfunction "1_1") (pintype "passive"))
      (node (ref "D6") (pin "1") (pinfunction "1_1") (pintype "passive"))
      (node (ref "D7") (pin "1") (pinfunction "1_1") (pintype "passive"))
      (node (ref "D8") (pin "1") (pinfunction "1_1") (pintype "passive"))
      (node (ref "R24") (pin "2") (pinfunction "2_2") (pintype "passive"))
    )
    (net (code "31") (name "Net-(U4A--)") (class "Default")
      (node (ref "C28") (pin "1") (pinfunction "1_1") (pintype "passive"))
      (node (ref "R14") (pin "2") (pinfunction "2_2") (pintype "passive"))
      (node (ref "R15") (pin "1") (pinfunction "1_1") (pintype "passive"))
      (node (ref "U4") (pin "2") (pinfunction "-_2") (pintype "passive"))
    )
    (net (code "32") (name "Net-(U4A-out)") (class "Default")
      (node (ref "C28") (pin "2") (pinfunction "2_2") (pintype "passive"))
      (node (ref "R11") (pin "1") (pinfunction "1_1") (pintype "passive"))
      (node (ref "R15") (pin "2") (pinfunction "2_2") (pintype "passive"))
      (node (ref "U4") (pin "1") (pinfunction "out_1") (pintype "passive"))
    )
    (net (code "33") (name "Net-(U4B--)") (class "Default")
      (node (ref "C27") (pin "1") (pinfunction "1_1") (pintype "passive"))
      (node (ref "R12") (pin "2") (pinfunction "2_2") (pintype "passive"))
      (node (ref "R13") (pin "1") (pinfunction "1_1") (pintype "passive"))
      (node (ref "U4") (pin "6") (pinfunction "-_6") (pintype "passive"))
    )
    (net (code "34") (name "Net-(U4B-out)") (class "Default")
      (node (ref "C27") (pin "2") (pinfunction "2_2") (pintype "passive"))
      (node (ref "R10") (pin "1") (pinfunction "1_1") (pintype "passive"))
      (node (ref "R13") (pin "2") (pinfunction "2_2") (pintype "passive"))
      (node (ref "U4") (pin "7") (pinfunction "out_7") (pintype "passive"))
    )
    (net (code "35") (name "Net-(U5-DOUT)") (class "Default")
      (node (ref "R23") (pin "2") (pinfunction "2_2") (pintype "passive"))
      (node (ref "U5") (pin "9") (pinfunction "DOUT_9") (pintype "passive"))
    )
    (net (code "36") (name "Net-(U5-VINL)") (class "Default")
      (node (ref "C37") (pin "1") (pinfunction "1_1") (pintype "passive"))
      (node (ref "R21") (pin "1") (pinfunction "1_1") (pintype "passive"))
      (node (ref "U5") (pin "13") (pinfunction "VINL_13") (pintype "passive"))
    )
    (net (code "37") (name "Net-(U5-VINR)") (class "Default")
      (node (ref "C33") (pin "1") (pinfunction "1_1") (pintype "passive"))
      (node (ref "R19") (pin "1") (pinfunction "1_1") (pintype "passive"))
      (node (ref "U5") (pin "14") (pinfunction "VINR_14") (pintype "passive"))
    )
    (net (code "38") (name "Net-(U5-VREF)") (class "Default")
      (node (ref "C34") (pin "2") (pinfunction "2_2") (pintype "passive"))
      (node (ref "C35") (pin "2") (pinfunction "2_2") (pintype "passive"))
      (node (ref "U5") (pin "1") (pinfunction "VREF_1") (pintype "passive"))
    )
    (net (code "39") (name "Net-(U6-AOUTL)") (class "Default")
      (node (ref "C41") (pin "2") (pinfunction "2_2") (pintype "passive"))
      (node (ref "U6") (pin "7") (pinfunction "AOUTL_7") (pintype "passive"))
    )
    (net (code "40") (name "Net-(U6-AOUTR)") (class "Default")
      (node (ref "C38") (pin "2") (pinfunction "2_2") (pintype "passive"))
      (node (ref "U6") (pin "10") (pinfunction "AOUTR_10") (pintype "passive"))
    )
    (net (code "41") (name "Net-(U6-FILT+)") (class "Default")
      (node (ref "C45") (pin "2") (pinfunction "2_2") (pintype "passive"))
      (node (ref "C46") (pin "2") (pinfunction "2_2") (pintype "passive"))
      (node (ref "U6") (pin "6") (pinfunction "FILT+_6") (pintype "passive"))
    )
    (net (code "42") (name "Net-(U6-VQ)") (class "Default")
      (node (ref "C43") (pin "2") (pinfunction "2_2") (pintype "passive"))
      (node (ref "C44") (pin "2") (pinfunction "2_2") (pintype "passive"))
      (node (ref "U6") (pin "5") (pinfunction "VQ_5") (pintype "passive"))
    )
    (net (code "43") (name "OUT_MIC_1") (class "Default")
      (node (ref "H2") (pin "1") (pinfunction "1_1") (pintype "passive"))
      (node (ref "R11") (pin "2") (pinfunction "2_2") (pintype "passive"))
      (node (ref "R20") (pin "2") (pinfunction "2_2") (pintype "passive"))
      (node (ref "TP9") (pin "1") (pinfunction "1_1") (pintype "passive"))
    )
    (net (code "44") (name "OUT_MIC_2") (class "Default")
      (node (ref "R10") (pin "2") (pinfunction "2_2") (pintype "passive"))
      (node (ref "R22") (pin "2") (pinfunction "2_2") (pintype "passive"))
    )
    (net (code "45") (name "V_REF") (class "Default")
      (node (ref "C18") (pin "1") (pinfunction "1_1") (pintype "passive"))
      (node (ref "C22") (pin "1") (pinfunction "1_1") (pintype "passive"))
      (node (ref "R8") (pin "2") (pinfunction "2_2") (pintype "passive"))
      (node (ref "R9") (pin "2") (pinfunction "2_2") (pintype "passive"))
      (node (ref "U4") (pin "3") (pinfunction "+_3") (pintype "passive"))
      (node (ref "U4") (pin "5") (pinfunction "+_5") (pintype "passive"))
    )
    (net (code "46") (name "WS") (class "Default")
      (node (ref "U5") (pin "7") (pinfunction "LRCK_7") (pintype "passive"))
      (node (ref "U6") (pin "3") (pinfunction "LRCK_3") (pintype "passive"))
    )
    (net (code "47") (name "unconnected-(H2-Pad2)") (class "Default")
      (node (ref "H2") (pin "2") (pinfunction "2_2") (pintype "passive+no_connect"))
    )
    (net (code "48") (name "unconnected-(TP5-Pad1)") (class "Default")
      (node (ref "TP5") (pin "1") (pinfunction "1_1") (pintype "passive"))
    )
    (net (code "49") (name "unconnected-(TP8-Pad1)") (class "Default")
      (node (ref "TP8") (pin "1") (pinfunction "1_1") (pintype "passive+no_connect"))
    )
  )
)
